# r2r_ladder_dac.net
KiCad netlist of a schematic drawn in EAGLE
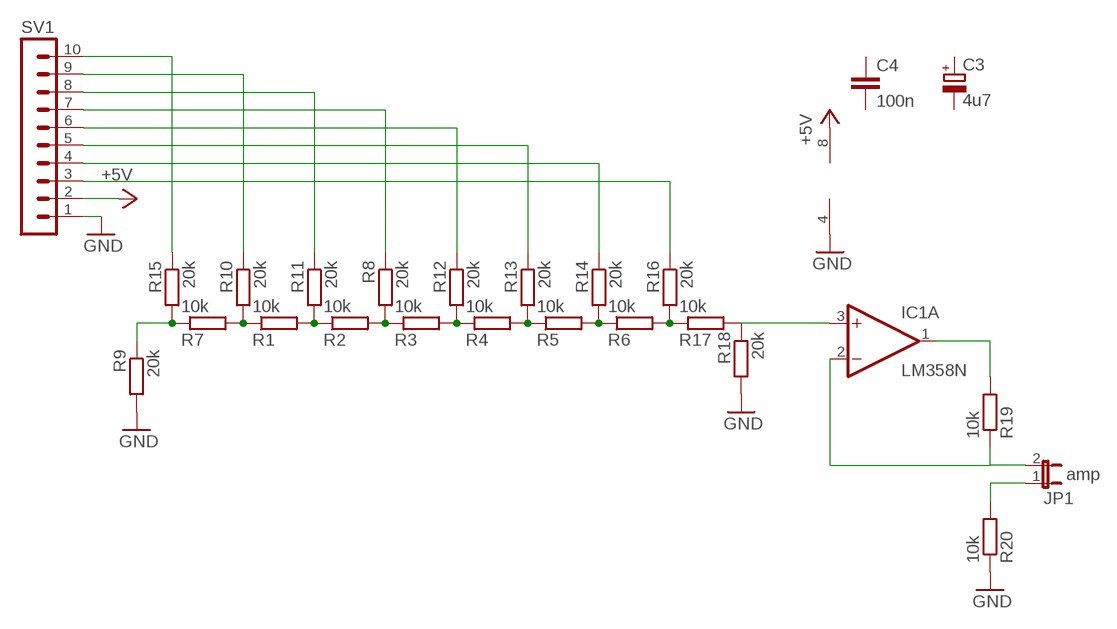
[diagram p0: schematic, sheet 1]

(export (version "E")
  (design (tool "Eeschema 10.0.6"))
  (components
    (comp (ref "C3")
      (value "4u7")
      (footprint "eagle-import:TT2D5")
      (libsource (lib "eagle-import") (part "CPOL-EUTT2D5"))
    )
    (comp (ref "C4")
      (value "100n")
      (footprint "eagle-import:C025-024X044")
      (libsource (lib "eagle-import") (part "C-EU025-024X044"))
    )
    (comp (ref "IC1")
      (value "LM358N")
      (footprint "eagle-import:DIL08")
      (libsource (lib "eagle-import") (part "LM358N"))
    )
    (comp (ref "JP1")
      (value "amp")
      (footprint "eagle-import:JP1")
      (libsource (lib "eagle-import") (part "JP1E"))
    )
    (comp (ref "R1")
      (value "10k")
      (footprint "eagle-import:0204V")
      (libsource (lib "eagle-import") (part "R-EU_0204/2V"))
    )
    (comp (ref "R2")
      (value "10k")
      (footprint "eagle-import:0204V")
      (libsource (lib "eagle-import") (part "R-EU_0204/2V"))
    )
    (comp (ref "R3")
      (value "10k")
      (footprint "eagle-import:0204V")
      (libsource (lib "eagle-import") (part "R-EU_0204/2V"))
    )
    (comp (ref "R4")
      (value "10k")
      (footprint "eagle-import:0204V")
      (libsource (lib "eagle-import") (part "R-EU_0204/2V"))
    )
    (comp (ref "R5")
      (value "10k")
      (footprint "eagle-import:0204V")
      (libsource (lib "eagle-import") (part "R-EU_0204/2V"))
    )
    (comp (ref "R6")
      (value "10k")
      (footprint "eagle-import:0204V")
      (libsource (lib "eagle-import") (part "R-EU_0204/2V"))
    )
    (comp (ref "R7")
      (value "10k")
      (footprint "eagle-import:0204V")
      (libsource (lib "eagle-import") (part "R-EU_0204/2V"))
    )
    (comp (ref "R8")
      (value "20k")
      (footprint "eagle-import:0207_10")
      (libsource (lib "eagle-import") (part "R-EU_0207/10"))
    )
    (comp (ref "R9")
      (value "20k")
      (footprint "eagle-import:0617_22")
      (libsource (lib "eagle-import") (part "R-EU_0617/22"))
    )
    (comp (ref "R10")
      (value "20k")
      (footprint "eagle-import:0207_10")
      (libsource (lib "eagle-import") (part "R-EU_0207/10"))
    )
    (comp (ref "R11")
      (value "20k")
      (footprint "eagle-import:0207_10")
      (libsource (lib "eagle-import") (part "R-EU_0207/10"))
    )
    (comp (ref "R12")
      (value "20k")
      (footprint "eagle-import:0207_10")
      (libsource (lib "eagle-import") (part "R-EU_0207/10"))
    )
    (comp (ref "R13")
      (value "20k")
      (footprint "eagle-import:0207_10")
      (libsource (lib "eagle-import") (part "R-EU_0207/10"))
    )
    (comp (ref "R14")
      (value "20k")
      (footprint "eagle-import:0207_10")
      (libsource (lib "eagle-import") (part "R-EU_0207/10"))
    )
    (comp (ref "R15")
      (value "20k")
      (footprint "eagle-import:0207_10")
      (libsource (lib "eagle-import") (part "R-EU_0207/10"))
    )
    (comp (ref "R16")
      (value "20k")
      (footprint "eagle-import:0207_10")
      (libsource (lib "eagle-import") (part "R-EU_0207/10"))
    )
    (comp (ref "R17")
      (value "10k")
      (footprint "eagle-import:0204_5")
      (libsource (lib "eagle-import") (part "R-EU_0204/5"))
    )
    (comp (ref "R18")
      (value "20k")
      (footprint "eagle-import:0207_10")
      (libsource (lib "eagle-import") (part "R-EU_0207/10"))
    )
    (comp (ref "R19")
      (value "10k")
      (footprint "eagle-import:0204V")
      (libsource (lib "eagle-import") (part "R-EU_0204/2V"))
    )
    (comp (ref "R20")
      (value "10k")
      (footprint "eagle-import:0204V")
      (libsource (lib "eagle-import") (part "R-EU_0204/2V"))
    )
    (comp (ref "SV1")
      (value "MA10-1W")
      (footprint "eagle-import:MA10-1W")
      (libsource (lib "eagle-import") (part "MA10-1W"))
    )
  )
  (nets
    (net (code "1") (name "+5V") (class "Default")
      (node (ref "IC1") (pin "8") (pinfunction "V+_8") (pintype "power_in"))
      (node (ref "SV1") (pin "2") (pinfunction "2_2") (pintype "passive"))
    )
    (net (code "2") (name "GND") (class "Default")
      (node (ref "IC1") (pin "4") (pinfunction "V-_4") (pintype "power_in"))
      (node (ref "R18") (pin "2") (pinfunction "2_2") (pintype "passive"))
      (node (ref "R20") (pin "1") (pinfunction "1_1") (pintype "passive"))
      (node (ref "R9") (pin "2") (pinfunction "2_2") (pintype "passive"))
      (node (ref "SV1") (pin "1") (pinfunction "1_1") (pintype "passive"))
    )
    (net (code "3") (name "Net-(IC1A-+IN)") (class "Default")
      (node (ref "IC1") (pin "3") (pinfunction "+IN_3") (pintype "input"))
      (node (ref "R17") (pin "2") (pinfunction "2_2") (pintype "passive"))
      (node (ref "R18") (pin "1") (pinfunction "1_1") (pintype "passive"))
    )
    (net (code "4") (name "Net-(IC1A--IN)") (class "Default")
      (node (ref "IC1") (pin "2") (pinfunction "-IN_2") (pintype "input"))
      (node (ref "JP1") (pin "2") (pinfunction "2_2") (pintype "passive"))
      (node (ref "R19") (pin "1") (pinfunction "1_1") (pintype "passive"))
    )
    (net (code "5") (name "Net-(IC1A-OUT)") (class "Default")
      (node (ref "IC1") (pin "1") (pinfunction "OUT_1") (pintype "output"))
      (node (ref "R19") (pin "2") (pinfunction "2_2") (pintype "passive"))
    )
    (net (code "6") (name "Net-(JP1-Pad1)") (class "Default")
      (node (ref "JP1") (pin "1") (pinfunction "1_1") (pintype "passive"))
      (node (ref "R20") (pin "2") (pinfunction "2_2") (pintype "passive"))
    )
    (net (code "7") (name "Net-(R1-Pad1)") (class "Default")
      (node (ref "R1") (pin "1") (pinfunction "1_1") (pintype "passive"))
      (node (ref "R10") (pin "2") (pinfunction "2_2") (pintype "passive"))
      (node (ref "R7") (pin "2") (pinfunction "2_2") (pintype "passive"))
    )
    (net (code "8") (name "Net-(R1-Pad2)") (class "Default")
      (node (ref "R1") (pin "2") (pinfunction "2_2") (pintype "passive"))
      (node (ref "R11") (pin "2") (pinfunction "2_2") (pintype "passive"))
      (node (ref "R2") (pin "1") (pinfunction "1_1") (pintype "passive"))
    )
    (net (code "9") (name "Net-(R2-Pad2)") (class "Default")
      (node (ref "R2") (pin "2") (pinfunction "2_2") (pintype "passive"))
      (node (ref "R3") (pin "1") (pinfunction "1_1") (pintype "passive"))
      (node (ref "R8") (pin "2") (pinfunction "2_2") (pintype "passive"))
    )
    (net (code "10") (name "Net-(R8-Pad1)") (class "Default")
      (node (ref "R8") (pin "1") (pinfunction "1_1") (pintype "passive"))
      (node (ref "SV1") (pin "7") (pinfunction "7_7") (pintype "passive"))
    )
    (net (code "11") (name "Net-(R10-Pad1)") (class "Default")
      (node (ref "R10") (pin "1") (pinfunction "1_1") (pintype "passive"))
      (node (ref "SV1") (pin "9") (pinfunction "9_9") (pintype "passive"))
    )
    (net (code "12") (name "Net-(R11-Pad1)") (class "Default")
      (node (ref "R11") (pin "1") (pinfunction "1_1") (pintype "passive"))
      (node (ref "SV1") (pin "8") (pinfunction "8_8") (pintype "passive"))
    )
    (net (code "13") (name "Net-(R12-Pad1)") (class "Default")
      (node (ref "R12") (pin "1") (pinfunction "1_1") (pintype "passive"))
      (node (ref "SV1") (pin "6") (pinfunction "6_6") (pintype "passive"))
    )
    (net (code "14") (name "Net-(R12-Pad2)") (class "Default")
      (node (ref "R12") (pin "2") (pinfunction "2_2") (pintype "passive"))
      (node (ref "R3") (pin "2") (pinfunction "2_2") (pintype "passive"))
      (node (ref "R4") (pin "1") (pinfunction "1_1") (pintype "passive"))
    )
    (net (code "15") (name "Net-(R13-Pad1)") (class "Default")
      (node (ref "R13") (pin "1") (pinfunction "1_1") (pintype "passive"))
      (node (ref "SV1") (pin "5") (pinfunction "5_5") (pintype "passive"))
    )
    (net (code "16") (name "Net-(R13-Pad2)") (class "Default")
      (node (ref "R13") (pin "2") (pinfunction "2_2") (pintype "passive"))
      (node (ref "R4") (pin "2") (pinfunction "2_2") (pintype "passive"))
      (node (ref "R5") (pin "1") (pinfunction "1_1") (pintype "passive"))
    )
    (net (code "17") (name "Net-(R14-Pad1)") (class "Default")
      (node (ref "R14") (pin "1") (pinfunction "1_1") (pintype "passive"))
      (node (ref "SV1") (pin "4") (pinfunction "4_4") (pintype "passive"))
    )
    (net (code "18") (name "Net-(R14-Pad2)") (class "Default")
      (node (ref "R14") (pin "2") (pinfunction "2_2") (pintype "passive"))
      (node (ref "R5") (pin "2") (pinfunction "2_2") (pintype "passive"))
      (node (ref "R6") (pin "1") (pinfunction "1_1") (pintype "passive"))
    )
    (net (code "19") (name "Net-(R15-Pad1)") (class "Default")
      (node (ref "R15") (pin "1") (pinfunction "1_1") (pintype "passive"))
      (node (ref "SV1") (pin "10") (pinfunction "10_10") (pintype "passive"))
    )
    (net (code "20") (name "Net-(R15-Pad2)") (class "Default")
      (node (ref "R15") (pin "2") (pinfunction "2_2") (pintype "passive"))
      (node (ref "R7") (pin "1") (pinfunction "1_1") (pintype "passive"))
      (node (ref "R9") (pin "1") (pinfunction "1_1") (pintype "passive"))
    )
    (net (code "21") (name "Net-(R16-Pad1)") (class "Default")
      (node (ref "R16") (pin "1") (pinfunction "1_1") (pintype "passive"))
      (node (ref "SV1") (pin "3") (pinfunction "3_3") (pintype "passive"))
    )
    (net (code "22") (name "Net-(R16-Pad2)") (class "Default")
      (node (ref "R16") (pin "2") (pinfunction "2_2") (pintype "passive"))
      (node (ref "R17") (pin "1") (pinfunction "1_1") (pintype "passive"))
      (node (ref "R6") (pin "2") (pinfunction "2_2") (pintype "passive"))
    )
    (net (code "23") (name "unconnected-(C3-Pad+)") (class "Default")
      (node (ref "C3") (pin "+") (pinfunction "+_+") (pintype "passive"))
    )
    (net (code "24") (name "unconnected-(C3-Pad-)") (class "Default")
      (node (ref "C3") (pin "-") (pinfunction "-_-") (pintype "passive"))
    )
    (net (code "25") (name "unconnected-(C4-Pad1)") (class "Default")
      (node (ref "C4") (pin "1") (pinfunction "1_1") (pintype "passive"))
    )
    (net (code "26") (name "unconnected-(C4-Pad2)") (class "Default")
      (node (ref "C4") (pin "2") (pinfunction "2_2") (pintype "passive"))
    )
  )
)
